# MouseGoggles_MonoHat-1-0.net
KiCad netlist of a schematic drawn in EAGLE
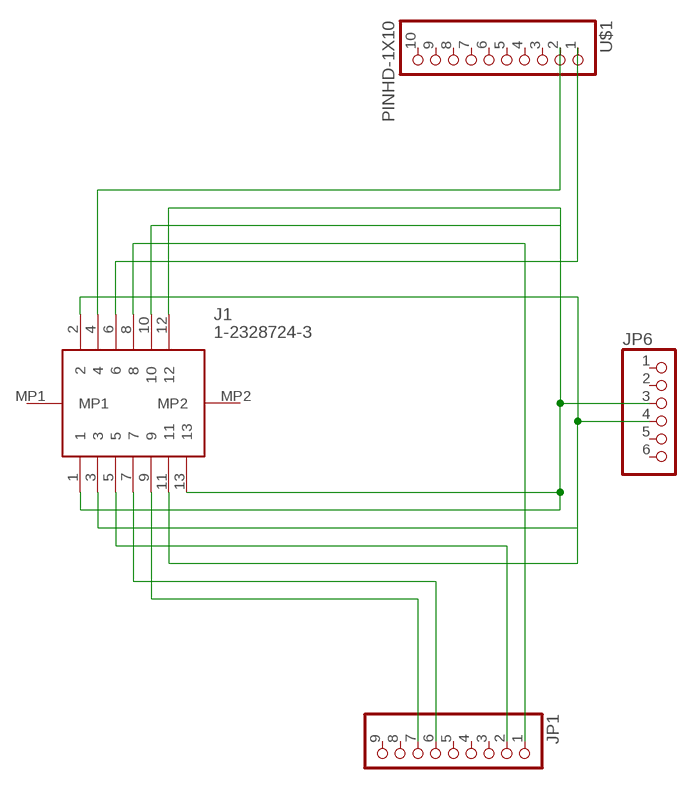
[diagram p0: schematic, sheet 1]

(export (version "E")
  (design (tool "Eeschema 10.0.6"))
  (components
    (comp (ref "J1")
      (value "1-2328724-3")
      (footprint "eagle-import:123287243")
      (fields (field (name "MOUSER_PART_NUMBER") "571-1-2328724-3"))
      (libsource (lib "eagle-import") (part "1-2328724-3"))
    )
    (comp (ref "JP1")
      (value "PINHD-1X9")
      (footprint "eagle-import:1X09-BIG")
      (libsource (lib "eagle-import") (part "PINHD-1X9"))
    )
    (comp (ref "JP6")
      (value "PINHD-1X6B")
      (footprint "eagle-import:1X06-BIG")
      (libsource (lib "eagle-import") (part "PINHD-1X6B"))
    )
    (comp (ref "U$1")
      (value "PINHD-1X10")
      (footprint "eagle-import:1X10-BIG")
      (libsource (lib "eagle-import") (part "PINHD-1X10"))
    )
  )
  (nets
    (net (code "1") (name "Net-(J1-Pad1)") (class "Default")
      (node (ref "J1") (pin "1") (pinfunction "1_1") (pintype "bidirectional"))
      (node (ref "J1") (pin "10") (pinfunction "10_10") (pintype "bidirectional"))
      (node (ref "J1") (pin "12") (pinfunction "12_12") (pintype "bidirectional"))
      (node (ref "J1") (pin "13") (pinfunction "13_13") (pintype "bidirectional"))
      (node (ref "JP6") (pin "3") (pinfunction "3_3") (pintype "passive"))
    )
    (net (code "2") (name "Net-(J1-Pad4)") (class "Default")
      (node (ref "J1") (pin "4") (pinfunction "4_4") (pintype "bidirectional"))
      (node (ref "U$1") (pin "2") (pinfunction "2_2") (pintype "passive"))
    )
    (net (code "3") (name "Net-(J1-Pad5)") (class "Default")
      (node (ref "J1") (pin "5") (pinfunction "5_5") (pintype "bidirectional"))
      (node (ref "JP1") (pin "2") (pinfunction "2_2") (pintype "passive"))
    )
    (net (code "4") (name "Net-(J1-Pad6)") (class "Default")
      (node (ref "J1") (pin "6") (pinfunction "6_6") (pintype "bidirectional"))
      (node (ref "U$1") (pin "1") (pinfunction "1_1") (pintype "passive"))
    )
    (net (code "5") (name "Net-(J1-Pad7)") (class "Default")
      (node (ref "J1") (pin "7") (pinfunction "7_7") (pintype "bidirectional"))
      (node (ref "JP1") (pin "6") (pinfunction "6_6") (pintype "passive"))
    )
    (net (code "6") (name "Net-(J1-Pad8)") (class "Default")
      (node (ref "J1") (pin "8") (pinfunction "8_8") (pintype "bidirectional"))
      (node (ref "JP1") (pin "1") (pinfunction "1_1") (pintype "passive"))
    )
    (net (code "7") (name "Net-(J1-Pad9)") (class "Default")
      (node (ref "J1") (pin "9") (pinfunction "9_9") (pintype "bidirectional"))
      (node (ref "JP1") (pin "7") (pinfunction "7_7") (pintype "passive"))
    )
    (net (code "8") (name "Net-(J1-Pad11)") (class "Default")
      (node (ref "J1") (pin "11") (pinfunction "11_11") (pintype "bidirectional"))
      (node (ref "J1") (pin "2") (pinfunction "2_2") (pintype "bidirectional"))
      (node (ref "J1") (pin "3") (pinfunction "3_3") (pintype "bidirectional"))
      (node (ref "JP6") (pin "4") (pinfunction "4_4") (pintype "passive"))
    )
    (net (code "9") (name "unconnected-(J1-PadMP1)") (class "Default")
      (node (ref "J1") (pin "MP1") (pinfunction "MP1_MP1") (pintype "bidirectional"))
    )
    (net (code "10") (name "unconnected-(J1-PadMP2)") (class "Default")
      (node (ref "J1") (pin "MP2") (pinfunction "MP2_MP2") (pintype "bidirectional"))
    )
    (net (code "11") (name "unconnected-(JP1-Pad3)") (class "Default")
      (node (ref "JP1") (pin "3") (pinfunction "3_3") (pintype "passive"))
    )
    (net (code "12") (name "unconnected-(JP1-Pad4)") (class "Default")
      (node (ref "JP1") (pin "4") (pinfunction "4_4") (pintype "passive"))
    )
    (net (code "13") (name "unconnected-(JP1-Pad5)") (class "Default")
      (node (ref "JP1") (pin "5") (pinfunction "5_5") (pintype "passive"))
    )
    (net (code "14") (name "unconnected-(JP1-Pad8)") (class "Default")
      (node (ref "JP1") (pin "8") (pinfunction "8_8") (pintype "passive"))
    )
    (net (code "15") (name "unconnected-(JP1-Pad9)") (class "Default")
      (node (ref "JP1") (pin "9") (pinfunction "9_9") (pintype "passive"))
    )
    (net (code "16") (name "unconnected-(JP6-Pad1)") (class "Default")
      (node (ref "JP6") (pin "1") (pinfunction "1_1") (pintype "passive"))
    )
    (net (code "17") (name "unconnected-(JP6-Pad2)") (class "Default")
      (node (ref "JP6") (pin "2") (pinfunction "2_2") (pintype "passive"))
    )
    (net (code "18") (name "unconnected-(JP6-Pad5)") (class "Default")
      (node (ref "JP6") (pin "5") (pinfunction "5_5") (pintype "passive"))
    )
    (net (code "19") (name "unconnected-(JP6-Pad6)") (class "Default")
      (node (ref "JP6") (pin "6") (pinfunction "6_6") (pintype "passive"))
    )
    (net (code "20") (name "unconnected-(U$1-Pad3)") (class "Default")
      (node (ref "U$1") (pin "3") (pinfunction "3_3") (pintype "passive"))
    )
    (net (code "21") (name "unconnected-(U$1-Pad4)") (class "Default")
      (node (ref "U$1") (pin "4") (pinfunction "4_4") (pintype "passive"))
    )
    (net (code "22") (name "unconnected-(U$1-Pad5)") (class "Default")
      (node (ref "U$1") (pin "5") (pinfunction "5_5") (pintype "passive"))
    )
    (net (code "23") (name "unconnected-(U$1-Pad6)") (class "Default")
      (node (ref "U$1") (pin "6") (pinfunction "6_6") (pintype "passive"))
    )
    (net (code "24") (name "unconnected-(U$1-Pad7)") (class "Default")
      (node (ref "U$1") (pin "7") (pinfunction "7_7") (pintype "passive"))
    )
    (net (code "25") (name "unconnected-(U$1-Pad8)") (class "Default")
      (node (ref "U$1") (pin "8") (pinfunction "8_8") (pintype "passive"))
    )
    (net (code "26") (name "unconnected-(U$1-Pad9)") (class "Default")
      (node (ref "U$1") (pin "9") (pinfunction "9_9") (pintype "passive"))
    )
    (net (code "27") (name "unconnected-(U$1-Pad10)") (class "Default")
      (node (ref "U$1") (pin "10") (pinfunction "10_10") (pintype "passive"))
    )
  )
)
